# PAGE2.net
KiCad netlist of a schematic drawn in Altium Designer
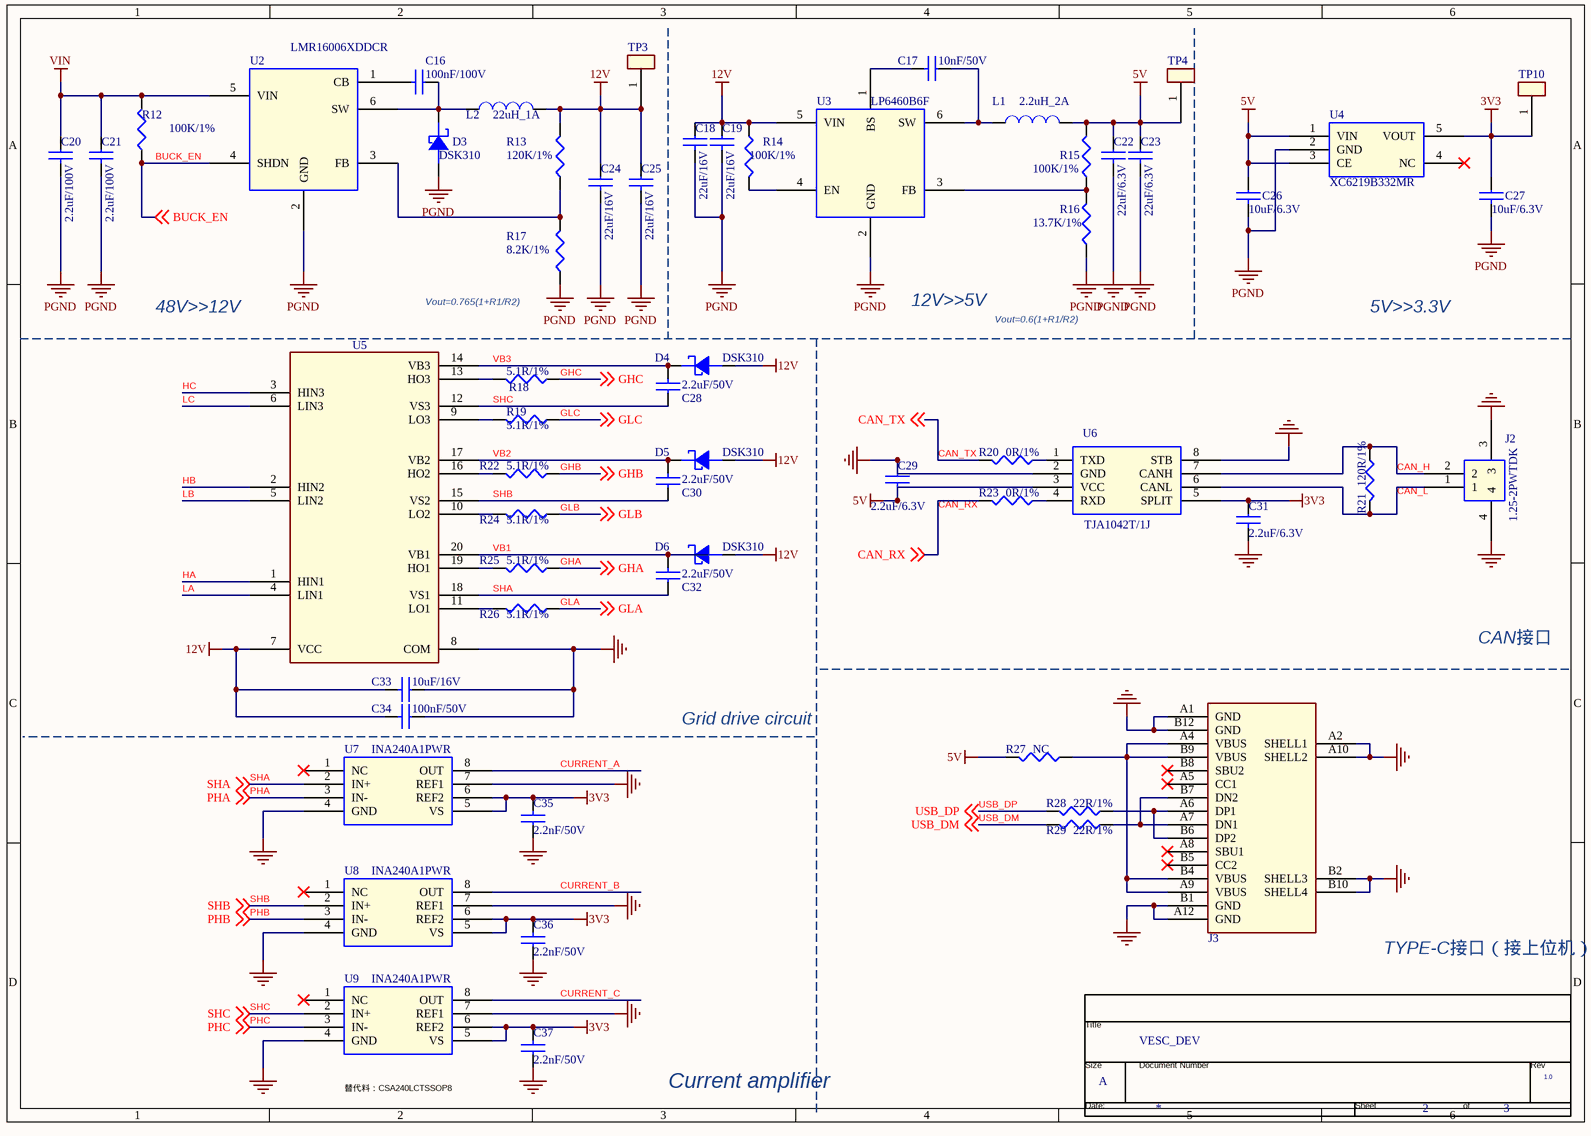
[diagram p0: PAGE2.SchDoc]

(export (version "E")
  (design (tool "Eeschema 10.0.6"))
  (components
    (comp (ref "C16") (value "100nF/100V") (footprint "C0603") (libsource (lib "*") (part "CAP NP")))
    (comp (ref "C17") (value "10nF/50V") (footprint "C0402") (libsource (lib "*") (part "CAP NP")))
    (comp (ref "C18") (value "22uF/16V") (footprint "C0805") (libsource (lib "*") (part "CAP NP")))
    (comp (ref "C19") (value "22uF/16V") (footprint "C0805") (libsource (lib "*") (part "CAP NP")))
    (comp (ref "C20") (value "2.2uF/100V") (footprint "C1206") (libsource (lib "*") (part "CAP NP")))
    (comp (ref "C21") (value "2.2uF/100V") (footprint "C1206") (libsource (lib "*") (part "CAP NP")))
    (comp (ref "C22") (value "22uF/6.3V") (footprint "C0805") (libsource (lib "*") (part "CAP NP")))
    (comp (ref "C23") (value "22uF/6.3V") (footprint "C0805") (libsource (lib "*") (part "CAP NP")))
    (comp (ref "C24") (value "22uF/16V") (footprint "C0805") (libsource (lib "*") (part "CAP NP")))
    (comp (ref "C25") (value "22uF/16V") (footprint "C0805") (libsource (lib "*") (part "CAP NP")))
    (comp (ref "C26") (value "10uF/6.3V") (footprint "C0402") (libsource (lib "*") (part "CAP NP")))
    (comp (ref "C27") (value "10uF/6.3V") (footprint "C0402") (libsource (lib "*") (part "CAP NP")))
    (comp (ref "C28") (value "2.2uF/50V") (footprint "C0603") (libsource (lib "*") (part "CAP NP")))
    (comp (ref "C29") (value "2.2uF/6.3V") (footprint "C0402") (libsource (lib "*") (part "CAP NP")))
    (comp (ref "C30") (value "2.2uF/50V") (footprint "C0603") (libsource (lib "*") (part "CAP NP")))
    (comp (ref "C31") (value "2.2uF/6.3V") (footprint "C0402") (libsource (lib "*") (part "CAP NP")))
    (comp (ref "C32") (value "2.2uF/50V") (footprint "C0603") (libsource (lib "*") (part "CAP NP")))
    (comp (ref "C33") (value "10uF/16V") (footprint "C0603") (libsource (lib "*") (part "CAP NP")))
    (comp (ref "C34") (value "100nF/50V") (footprint "C0402") (libsource (lib "*") (part "CAP NP")))
    (comp (ref "C35") (value "2.2nF/50V") (footprint "C0402") (libsource (lib "*") (part "CAP NP")))
    (comp (ref "C36") (value "2.2nF/50V") (footprint "C0402") (libsource (lib "*") (part "CAP NP")))
    (comp (ref "C37") (value "2.2nF/50V") (footprint "C0402") (libsource (lib "*") (part "CAP NP")))
    (comp (ref "D3") (value "DSK310") (footprint "SOD-123F") (libsource (lib "*") (part "DIODE SCHOTTKY21")))
    (comp (ref "D4") (value "DSK310") (footprint "SOD-123F") (libsource (lib "*") (part "DIODE SCHOTTKY21")))
    (comp (ref "D5") (value "DSK310") (footprint "SOD-123F") (libsource (lib "*") (part "DIODE SCHOTTKY21")))
    (comp (ref "D6") (value "DSK310") (footprint "SOD-123F") (libsource (lib "*") (part "DIODE SCHOTTKY21")))
    (comp (ref "J2")
      (value "1.25-2PWTDK")
      (footprint "SMD-2P-1_25")
      (libsource (lib "*") (part "1.25-2PWTDK"))
    )
    (comp (ref "J3")
      (value "TYPE-C 16PLC-H10.0")
      (footprint "TYPE-C-TH_16PLC-H10.0")
      (description "连接器类型:Type-C;标准:USB 3.1;公母:母;安装方式:直插;触点数量:16P;端口数量:1;额定电流 - 电源:5A;触头材质:-;触头镀层:-;工作温度范围:-40℃~+85℃;")
      (fields (field (name "MANUFACTURER") "SHOU HAN(首韩)"))
      (libsource (lib "VESC_DEVICE_Library") (part "TYPE-C 16PLC-H10.0"))
    )
    (comp (ref "L1") (value "2.2uH_2A") (footprint "L4020") (libsource (lib "*") (part "INDUCTOR")))
    (comp (ref "L2") (value "22uH_1A") (footprint "L4020") (libsource (lib "*") (part "INDUCTOR")))
    (comp (ref "R12") (value "100K/1%") (footprint "R0402") (libsource (lib "*") (part "RESISTOR")))
    (comp (ref "R13") (value "120K/1%") (footprint "R0402") (libsource (lib "*") (part "RESISTOR")))
    (comp (ref "R14") (value "100K/1%") (footprint "R0402") (libsource (lib "*") (part "RESISTOR")))
    (comp (ref "R15") (value "100K/1%") (footprint "R0402") (libsource (lib "*") (part "RESISTOR")))
    (comp (ref "R16") (value "13.7K/1%") (footprint "R0402") (libsource (lib "*") (part "RESISTOR")))
    (comp (ref "R17") (value "8.2K/1%") (footprint "R0402") (libsource (lib "*") (part "RESISTOR")))
    (comp (ref "R18") (value "5.1R/1%") (footprint "R0402") (libsource (lib "*") (part "RESISTOR")))
    (comp (ref "R19") (value "5.1R/1%") (footprint "R0402") (libsource (lib "*") (part "RESISTOR")))
    (comp (ref "R20") (value "0R/1%") (footprint "R0402") (libsource (lib "*") (part "RESISTOR")))
    (comp (ref "R21") (value "120R/1%") (footprint "R0402") (libsource (lib "*") (part "RESISTOR")))
    (comp (ref "R22") (value "5.1R/1%") (footprint "R0402") (libsource (lib "*") (part "RESISTOR")))
    (comp (ref "R23") (value "0R/1%") (footprint "R0402") (libsource (lib "*") (part "RESISTOR")))
    (comp (ref "R24") (value "5.1R/1%") (footprint "R0402") (libsource (lib "*") (part "RESISTOR")))
    (comp (ref "R25") (value "5.1R/1%") (footprint "R0402") (libsource (lib "*") (part "RESISTOR")))
    (comp (ref "R26") (value "5.1R/1%") (footprint "R0402") (libsource (lib "*") (part "RESISTOR")))
    (comp (ref "R27") (value "NC") (footprint "R0603") (libsource (lib "*") (part "RESISTOR")))
    (comp (ref "R28") (value "22R/1%") (footprint "R0402") (libsource (lib "*") (part "RESISTOR")))
    (comp (ref "R29") (value "22R/1%") (footprint "R0402") (libsource (lib "*") (part "RESISTOR")))
    (comp (ref "TP3")
      (value "TEST POINT")
      (footprint "test_point_100_smd")
      (libsource (lib "VESC_DEVICE_Library") (part "TEST POINT"))
    )
    (comp (ref "TP4")
      (value "TEST POINT")
      (footprint "test_point_100_smd")
      (libsource (lib "VESC_DEVICE_Library") (part "TEST POINT"))
    )
    (comp (ref "TP10")
      (value "TEST POINT")
      (footprint "test_point_100_smd")
      (libsource (lib "VESC_DEVICE_Library") (part "TEST POINT"))
    )
    (comp (ref "U2")
      (value "LMR16006XDDCR")
      (footprint "SOT-23-6")
      (libsource (lib "*") (part "LMR16006XDDCR"))
    )
    (comp (ref "U3") (value "LP6460B6F") (footprint "SOT-23-6") (libsource (lib "*") (part "LP6460B6F")))
    (comp (ref "U4")
      (value "XC6219B332MR")
      (footprint "SOT-23-5")
      (libsource (lib "*") (part "XC6219B332MR"))
    )
    (comp (ref "U5")
      (value "FD6288T")
      (footprint "TSSOP-20")
      (libsource (lib "VESC_DEVICE_Library") (part "FD6288T"))
    )
    (comp (ref "U6") (value "TJA1042T/1J") (footprint "SOP-8") (libsource (lib "*") (part "TJA1042T/1J")))
    (comp (ref "U7") (value "INA240A1PWR") (footprint "TSSOP-8") (libsource (lib "*") (part "INA240A1PWR")))
    (comp (ref "U8") (value "INA240A1PWR") (footprint "TSSOP-8") (libsource (lib "*") (part "INA240A1PWR")))
    (comp (ref "U9") (value "INA240A1PWR") (footprint "TSSOP-8") (libsource (lib "*") (part "INA240A1PWR")))
  )
  (nets
    (net (code "1") (name "/CAN_H") (class "Default")
      (node (ref "J2") (pin "2") (pinfunction "2_2") (pintype "passive"))
      (node (ref "R21") (pin "1") (pinfunction "1_1") (pintype "passive"))
      (node (ref "U6") (pin "7") (pinfunction "CANH_7") (pintype "passive"))
    )
    (net (code "2") (name "/CAN_L") (class "Default")
      (node (ref "J2") (pin "1") (pinfunction "1_1") (pintype "passive"))
      (node (ref "R21") (pin "2") (pinfunction "2_2") (pintype "passive"))
      (node (ref "U6") (pin "6") (pinfunction "CANL_6") (pintype "passive"))
    )
    (net (code "3") (name "/CURRENT_A") (class "Default")
      (node (ref "U7") (pin "8") (pinfunction "OUT_8") (pintype "passive"))
    )
    (net (code "4") (name "/CURRENT_B") (class "Default")
      (node (ref "U8") (pin "8") (pinfunction "OUT_8") (pintype "passive"))
    )
    (net (code "5") (name "/CURRENT_C") (class "Default")
      (node (ref "U9") (pin "8") (pinfunction "OUT_8") (pintype "passive"))
    )
    (net (code "6") (name "/HA") (class "Default")
      (node (ref "U5") (pin "1") (pinfunction "HIN1_1") (pintype "passive"))
    )
    (net (code "7") (name "/HB") (class "Default")
      (node (ref "U5") (pin "2") (pinfunction "HIN2_2") (pintype "passive"))
    )
    (net (code "8") (name "/HC") (class "Default")
      (node (ref "U5") (pin "3") (pinfunction "HIN3_3") (pintype "passive"))
    )
    (net (code "9") (name "/LA") (class "Default")
      (node (ref "U5") (pin "4") (pinfunction "LIN1_4") (pintype "passive"))
    )
    (net (code "10") (name "/LB") (class "Default")
      (node (ref "U5") (pin "5") (pinfunction "LIN2_5") (pintype "passive"))
    )
    (net (code "11") (name "/LC") (class "Default")
      (node (ref "U5") (pin "6") (pinfunction "LIN3_6") (pintype "passive"))
    )
    (net (code "12") (name "/VB1") (class "Default")
      (node (ref "C32") (pin "2") (pinfunction "2_2") (pintype "passive"))
      (node (ref "D6") (pin "1") (pinfunction "K_1") (pintype "passive"))
      (node (ref "U5") (pin "20") (pinfunction "VB1_20") (pintype "passive"))
    )
    (net (code "13") (name "/VB2") (class "Default")
      (node (ref "C30") (pin "2") (pinfunction "2_2") (pintype "passive"))
      (node (ref "D5") (pin "1") (pinfunction "K_1") (pintype "passive"))
      (node (ref "U5") (pin "17") (pinfunction "VB2_17") (pintype "passive"))
    )
    (net (code "14") (name "/VB3") (class "Default")
      (node (ref "C28") (pin "2") (pinfunction "2_2") (pintype "passive"))
      (node (ref "D4") (pin "1") (pinfunction "K_1") (pintype "passive"))
      (node (ref "U5") (pin "14") (pinfunction "VB3_14") (pintype "passive"))
    )
    (net (code "15") (name "3V3") (class "Default")
      (node (ref "C27") (pin "1") (pinfunction "1_1") (pintype "passive"))
      (node (ref "C31") (pin "1") (pinfunction "1_1") (pintype "passive"))
      (node (ref "C35") (pin "2") (pinfunction "2_2") (pintype "passive"))
      (node (ref "C36") (pin "2") (pinfunction "2_2") (pintype "passive"))
      (node (ref "C37") (pin "2") (pinfunction "2_2") (pintype "passive"))
      (node (ref "TP10") (pin "1") (pinfunction "1_1") (pintype "passive"))
      (node (ref "U4") (pin "5") (pinfunction "VOUT_5") (pintype "passive"))
      (node (ref "U6") (pin "5") (pinfunction "SPLIT_5") (pintype "passive"))
      (node (ref "U7") (pin "5") (pinfunction "VS_5") (pintype "passive"))
      (node (ref "U7") (pin "6") (pinfunction "REF2_6") (pintype "passive"))
      (node (ref "U8") (pin "5") (pinfunction "VS_5") (pintype "passive"))
      (node (ref "U8") (pin "6") (pinfunction "REF2_6") (pintype "passive"))
      (node (ref "U9") (pin "5") (pinfunction "VS_5") (pintype "passive"))
      (node (ref "U9") (pin "6") (pinfunction "REF2_6") (pintype "passive"))
    )
    (net (code "16") (name "5V") (class "Default")
      (node (ref "C22") (pin "1") (pinfunction "1_1") (pintype "passive"))
      (node (ref "C23") (pin "1") (pinfunction "1_1") (pintype "passive"))
      (node (ref "C26") (pin "1") (pinfunction "1_1") (pintype "passive"))
      (node (ref "C29") (pin "2") (pinfunction "2_2") (pintype "passive"))
      (node (ref "L1") (pin "2") (pinfunction "2_2") (pintype "passive"))
      (node (ref "R15") (pin "2") (pinfunction "2_2") (pintype "passive"))
      (node (ref "R27") (pin "2") (pinfunction "2_2") (pintype "passive"))
      (node (ref "TP4") (pin "1") (pinfunction "1_1") (pintype "passive"))
      (node (ref "U4") (pin "1") (pinfunction "VIN_1") (pintype "passive"))
      (node (ref "U4") (pin "3") (pinfunction "CE_3") (pintype "passive"))
      (node (ref "U6") (pin "3") (pinfunction "VCC_3") (pintype "passive"))
    )
    (net (code "17") (name "12V") (class "Default")
      (node (ref "C18") (pin "1") (pinfunction "1_1") (pintype "passive"))
      (node (ref "C19") (pin "1") (pinfunction "1_1") (pintype "passive"))
      (node (ref "C24") (pin "1") (pinfunction "1_1") (pintype "passive"))
      (node (ref "C25") (pin "1") (pinfunction "1_1") (pintype "passive"))
      (node (ref "C33") (pin "2") (pinfunction "2_2") (pintype "passive"))
      (node (ref "C34") (pin "2") (pinfunction "2_2") (pintype "passive"))
      (node (ref "D4") (pin "2") (pinfunction "A_2") (pintype "passive"))
      (node (ref "D5") (pin "2") (pinfunction "A_2") (pintype "passive"))
      (node (ref "D6") (pin "2") (pinfunction "A_2") (pintype "passive"))
      (node (ref "L2") (pin "2") (pinfunction "2_2") (pintype "passive"))
      (node (ref "R13") (pin "2") (pinfunction "2_2") (pintype "passive"))
      (node (ref "R14") (pin "1") (pinfunction "1_1") (pintype "passive"))
      (node (ref "TP3") (pin "1") (pinfunction "1_1") (pintype "passive"))
      (node (ref "U3") (pin "5") (pinfunction "VIN_5") (pintype "passive"))
      (node (ref "U5") (pin "7") (pinfunction "VCC_7") (pintype "power_in"))
    )
    (net (code "18") (name "BUCK_EN") (class "Default")
      (node (ref "R12") (pin "1") (pinfunction "1_1") (pintype "passive"))
      (node (ref "U2") (pin "4") (pinfunction "SHDN_4") (pintype "passive"))
    )
    (net (code "19") (name "CAN_RX") (class "Default")
      (node (ref "R23") (pin "2") (pinfunction "2_2") (pintype "passive"))
    )
    (net (code "20") (name "CAN_TX") (class "Default")
      (node (ref "R20") (pin "2") (pinfunction "2_2") (pintype "passive"))
    )
    (net (code "21") (name "GHA") (class "Default")
      (node (ref "R25") (pin "1") (pinfunction "1_1") (pintype "passive"))
    )
    (net (code "22") (name "GHB") (class "Default")
      (node (ref "R22") (pin "1") (pinfunction "1_1") (pintype "passive"))
    )
    (net (code "23") (name "GHC") (class "Default")
      (node (ref "R18") (pin "1") (pinfunction "1_1") (pintype "passive"))
    )
    (net (code "24") (name "GLA") (class "Default")
      (node (ref "R26") (pin "1") (pinfunction "1_1") (pintype "passive"))
    )
    (net (code "25") (name "GLB") (class "Default")
      (node (ref "R24") (pin "1") (pinfunction "1_1") (pintype "passive"))
    )
    (net (code "26") (name "GLC") (class "Default")
      (node (ref "R19") (pin "1") (pinfunction "1_1") (pintype "passive"))
    )
    (net (code "27") (name "GND") (class "Default")
      (node (ref "C29") (pin "1") (pinfunction "1_1") (pintype "passive"))
      (node (ref "C31") (pin "2") (pinfunction "2_2") (pintype "passive"))
      (node (ref "C33") (pin "1") (pinfunction "1_1") (pintype "passive"))
      (node (ref "C34") (pin "1") (pinfunction "1_1") (pintype "passive"))
      (node (ref "C35") (pin "1") (pinfunction "1_1") (pintype "passive"))
      (node (ref "C36") (pin "1") (pinfunction "1_1") (pintype "passive"))
      (node (ref "C37") (pin "1") (pinfunction "1_1") (pintype "passive"))
      (node (ref "J2") (pin "3") (pinfunction "3_3") (pintype "passive"))
      (node (ref "J2") (pin "4") (pinfunction "4_4") (pintype "passive"))
      (node (ref "J3") (pin "A1") (pinfunction "GND_A1") (pintype "power_in"))
      (node (ref "J3") (pin "A10") (pinfunction "SHELL2_A10") (pintype "power_in"))
      (node (ref "J3") (pin "A12") (pinfunction "GND_A12") (pintype "power_in"))
      (node (ref "J3") (pin "A2") (pinfunction "SHELL1_A2") (pintype "power_in"))
      (node (ref "J3") (pin "B1") (pinfunction "GND_B1") (pintype "power_in"))
      (node (ref "J3") (pin "B10") (pinfunction "SHELL4_B10") (pintype "power_in"))
      (node (ref "J3") (pin "B12") (pinfunction "GND_B12") (pintype "power_in"))
      (node (ref "J3") (pin "B2") (pinfunction "SHELL3_B2") (pintype "power_in"))
      (node (ref "U5") (pin "8") (pinfunction "COM_8") (pintype "power_in"))
      (node (ref "U6") (pin "2") (pinfunction "GND_2") (pintype "passive"))
      (node (ref "U6") (pin "8") (pinfunction "STB_8") (pintype "passive"))
      (node (ref "U7") (pin "4") (pinfunction "GND_4") (pintype "passive"))
      (node (ref "U7") (pin "7") (pinfunction "REF1_7") (pintype "passive"))
      (node (ref "U8") (pin "4") (pinfunction "GND_4") (pintype "passive"))
      (node (ref "U8") (pin "7") (pinfunction "REF1_7") (pintype "passive"))
      (node (ref "U9") (pin "4") (pinfunction "GND_4") (pintype "passive"))
      (node (ref "U9") (pin "7") (pinfunction "REF1_7") (pintype "passive"))
    )
    (net (code "28") (name "Net-(D3-K)") (class "Default")
      (node (ref "C16") (pin "1") (pinfunction "1_1") (pintype "passive"))
      (node (ref "D3") (pin "1") (pinfunction "K_1") (pintype "passive"))
      (node (ref "L2") (pin "1") (pinfunction "1_1") (pintype "passive"))
      (node (ref "U2") (pin "6") (pinfunction "SW_6") (pintype "passive"))
    )
    (net (code "29") (name "Net-(J3-DN1)") (class "Default")
      (node (ref "J3") (pin "A7") (pinfunction "DN1_A7") (pintype "passive"))
      (node (ref "J3") (pin "B7") (pinfunction "DN2_B7") (pintype "passive"))
      (node (ref "R29") (pin "1") (pinfunction "1_1") (pintype "passive"))
    )
    (net (code "30") (name "Net-(J3-DP1)") (class "Default")
      (node (ref "J3") (pin "A6") (pinfunction "DP1_A6") (pintype "passive"))
      (node (ref "J3") (pin "B6") (pinfunction "DP2_B6") (pintype "passive"))
      (node (ref "R28") (pin "1") (pinfunction "1_1") (pintype "passive"))
    )
    (net (code "31") (name "Net-(J3-VBUS-PadA4)") (class "Default")
      (node (ref "J3") (pin "A4") (pinfunction "VBUS_A4") (pintype "power_in"))
      (node (ref "J3") (pin "A9") (pinfunction "VBUS_A9") (pintype "power_in"))
      (node (ref "J3") (pin "B4") (pinfunction "VBUS_B4") (pintype "power_in"))
      (node (ref "J3") (pin "B9") (pinfunction "VBUS_B9") (pintype "power_in"))
      (node (ref "R27") (pin "1") (pinfunction "1_1") (pintype "passive"))
    )
    (net (code "32") (name "Net-(U2-CB)") (class "Default")
      (node (ref "C16") (pin "2") (pinfunction "2_2") (pintype "passive"))
      (node (ref "U2") (pin "1") (pinfunction "CB_1") (pintype "passive"))
    )
    (net (code "33") (name "Net-(U2-FB)") (class "Default")
      (node (ref "R13") (pin "1") (pinfunction "1_1") (pintype "passive"))
      (node (ref "R17") (pin "2") (pinfunction "2_2") (pintype "passive"))
      (node (ref "U2") (pin "3") (pinfunction "FB_3") (pintype "passive"))
    )
    (net (code "34") (name "Net-(U3-BS)") (class "Default")
      (node (ref "C17") (pin "2") (pinfunction "2_2") (pintype "passive"))
      (node (ref "U3") (pin "1") (pinfunction "BS_1") (pintype "passive"))
    )
    (net (code "35") (name "Net-(U3-EN)") (class "Default")
      (node (ref "R14") (pin "2") (pinfunction "2_2") (pintype "passive"))
      (node (ref "U3") (pin "4") (pinfunction "EN_4") (pintype "passive"))
    )
    (net (code "36") (name "Net-(U3-FB)") (class "Default")
      (node (ref "R15") (pin "1") (pinfunction "1_1") (pintype "passive"))
      (node (ref "R16") (pin "2") (pinfunction "2_2") (pintype "passive"))
      (node (ref "U3") (pin "3") (pinfunction "FB_3") (pintype "passive"))
    )
    (net (code "37") (name "Net-(U3-SW)") (class "Default")
      (node (ref "C17") (pin "1") (pinfunction "1_1") (pintype "passive"))
      (node (ref "L1") (pin "1") (pinfunction "1_1") (pintype "passive"))
      (node (ref "U3") (pin "6") (pinfunction "SW_6") (pintype "passive"))
    )
    (net (code "38") (name "Net-(U5-HO1)") (class "Default")
      (node (ref "R25") (pin "2") (pinfunction "2_2") (pintype "passive"))
      (node (ref "U5") (pin "19") (pinfunction "HO1_19") (pintype "passive"))
    )
    (net (code "39") (name "Net-(U5-HO2)") (class "Default")
      (node (ref "R22") (pin "2") (pinfunction "2_2") (pintype "passive"))
      (node (ref "U5") (pin "16") (pinfunction "HO2_16") (pintype "passive"))
    )
    (net (code "40") (name "Net-(U5-HO3)") (class "Default")
      (node (ref "R18") (pin "2") (pinfunction "2_2") (pintype "passive"))
      (node (ref "U5") (pin "13") (pinfunction "HO3_13") (pintype "passive"))
    )
    (net (code "41") (name "Net-(U5-LO1)") (class "Default")
      (node (ref "R26") (pin "2") (pinfunction "2_2") (pintype "passive"))
      (node (ref "U5") (pin "11") (pinfunction "LO1_11") (pintype "passive"))
    )
    (net (code "42") (name "Net-(U5-LO2)") (class "Default")
      (node (ref "R24") (pin "2") (pinfunction "2_2") (pintype "passive"))
      (node (ref "U5") (pin "10") (pinfunction "LO2_10") (pintype "passive"))
    )
    (net (code "43") (name "Net-(U5-LO3)") (class "Default")
      (node (ref "R19") (pin "2") (pinfunction "2_2") (pintype "passive"))
      (node (ref "U5") (pin "9") (pinfunction "LO3_9") (pintype "passive"))
    )
    (net (code "44") (name "Net-(U6-RXD)") (class "Default")
      (node (ref "R23") (pin "1") (pinfunction "1_1") (pintype "passive"))
      (node (ref "U6") (pin "4") (pinfunction "RXD_4") (pintype "passive"))
    )
    (net (code "45") (name "Net-(U6-TXD)") (class "Default")
      (node (ref "R20") (pin "1") (pinfunction "1_1") (pintype "passive"))
      (node (ref "U6") (pin "1") (pinfunction "TXD_1") (pintype "passive"))
    )
    (net (code "46") (name "PGND") (class "Default")
      (node (ref "C18") (pin "2") (pinfunction "2_2") (pintype "passive"))
      (node (ref "C19") (pin "2") (pinfunction "2_2") (pintype "passive"))
      (node (ref "C20") (pin "2") (pinfunction "2_2") (pintype "passive"))
      (node (ref "C21") (pin "2") (pinfunction "2_2") (pintype "passive"))
      (node (ref "C22") (pin "2") (pinfunction "2_2") (pintype "passive"))
      (node (ref "C23") (pin "2") (pinfunction "2_2") (pintype "passive"))
      (node (ref "C24") (pin "2") (pinfunction "2_2") (pintype "passive"))
      (node (ref "C25") (pin "2") (pinfunction "2_2") (pintype "passive"))
      (node (ref "C26") (pin "2") (pinfunction "2_2") (pintype "passive"))
      (node (ref "C27") (pin "2") (pinfunction "2_2") (pintype "passive"))
      (node (ref "D3") (pin "2") (pinfunction "A_2") (pintype "passive"))
      (node (ref "R16") (pin "1") (pinfunction "1_1") (pintype "passive"))
      (node (ref "R17") (pin "1") (pinfunction "1_1") (pintype "passive"))
      (node (ref "U2") (pin "2") (pinfunction "GND_2") (pintype "passive"))
      (node (ref "U3") (pin "2") (pinfunction "GND_2") (pintype "passive"))
      (node (ref "U4") (pin "2") (pinfunction "GND_2") (pintype "passive"))
    )
    (net (code "47") (name "PHA") (class "Default")
      (node (ref "U7") (pin "3") (pinfunction "IN-_3") (pintype "passive"))
    )
    (net (code "48") (name "PHB") (class "Default")
      (node (ref "U8") (pin "3") (pinfunction "IN-_3") (pintype "passive"))
    )
    (net (code "49") (name "PHC") (class "Default")
      (node (ref "U9") (pin "3") (pinfunction "IN-_3") (pintype "passive"))
    )
    (net (code "50") (name "SHA") (class "Default")
      (node (ref "C32") (pin "1") (pinfunction "1_1") (pintype "passive"))
      (node (ref "U5") (pin "18") (pinfunction "VS1_18") (pintype "passive"))
      (node (ref "U7") (pin "2") (pinfunction "IN+_2") (pintype "passive"))
    )
    (net (code "51") (name "SHB") (class "Default")
      (node (ref "C30") (pin "1") (pinfunction "1_1") (pintype "passive"))
      (node (ref "U5") (pin "15") (pinfunction "VS2_15") (pintype "passive"))
      (node (ref "U8") (pin "2") (pinfunction "IN+_2") (pintype "passive"))
    )
    (net (code "52") (name "SHC") (class "Default")
      (node (ref "C28") (pin "1") (pinfunction "1_1") (pintype "passive"))
      (node (ref "U5") (pin "12") (pinfunction "VS3_12") (pintype "passive"))
      (node (ref "U9") (pin "2") (pinfunction "IN+_2") (pintype "passive"))
    )
    (net (code "53") (name "USB_DM") (class "Default")
      (node (ref "R29") (pin "2") (pinfunction "2_2") (pintype "passive"))
    )
    (net (code "54") (name "USB_DP") (class "Default")
      (node (ref "R28") (pin "2") (pinfunction "2_2") (pintype "passive"))
    )
    (net (code "55") (name "VIN") (class "Default")
      (node (ref "C20") (pin "1") (pinfunction "1_1") (pintype "passive"))
      (node (ref "C21") (pin "1") (pinfunction "1_1") (pintype "passive"))
      (node (ref "R12") (pin "2") (pinfunction "2_2") (pintype "passive"))
      (node (ref "U2") (pin "5") (pinfunction "VIN_5") (pintype "passive"))
    )
    (net (code "56") (name "unconnected-(J3-CC1-PadA5)") (class "Default")
      (node (ref "J3") (pin "A5") (pinfunction "CC1_A5") (pintype "passive+no_connect"))
    )
    (net (code "57") (name "unconnected-(J3-CC2-PadB5)") (class "Default")
      (node (ref "J3") (pin "B5") (pinfunction "CC2_B5") (pintype "passive+no_connect"))
    )
    (net (code "58") (name "unconnected-(J3-SBU1-PadA8)") (class "Default")
      (node (ref "J3") (pin "A8") (pinfunction "SBU1_A8") (pintype "passive+no_connect"))
    )
    (net (code "59") (name "unconnected-(J3-SBU2-PadB8)") (class "Default")
      (node (ref "J3") (pin "B8") (pinfunction "SBU2_B8") (pintype "passive+no_connect"))
    )
    (net (code "60") (name "unconnected-(U4-NC-Pad4)") (class "Default")
      (node (ref "U4") (pin "4") (pinfunction "NC_4") (pintype "passive+no_connect"))
    )
    (net (code "61") (name "unconnected-(U7-NC-Pad1)") (class "Default")
      (node (ref "U7") (pin "1") (pinfunction "NC_1") (pintype "passive+no_connect"))
    )
    (net (code "62") (name "unconnected-(U8-NC-Pad1)") (class "Default")
      (node (ref "U8") (pin "1") (pinfunction "NC_1") (pintype "passive+no_connect"))
    )
    (net (code "63") (name "unconnected-(U9-NC-Pad1)") (class "Default")
      (node (ref "U9") (pin "1") (pinfunction "NC_1") (pintype "passive+no_connect"))
    )
  )
)
